# schematic_design.net
KiCad netlist of a schematic drawn in EAGLE
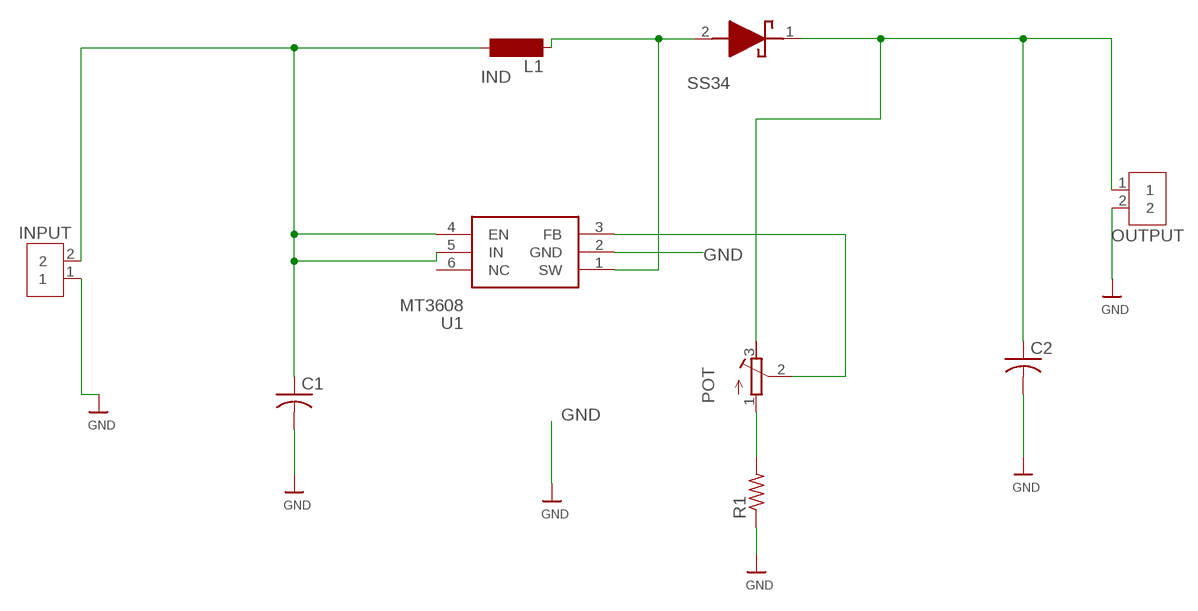
[diagram p0: schematic, sheet 1]

(export (version "E")
  (design (tool "Eeschema 10.0.6"))
  (components
    (comp (ref "C1")
      (value "C-USC0805")
      (footprint "eagle-import:C0805")
      (libsource (lib "eagle-import") (part "C-USC0805"))
    )
    (comp (ref "C2")
      (value "C-USC0805")
      (footprint "eagle-import:C0805")
      (libsource (lib "eagle-import") (part "C-USC0805"))
    )
    (comp (ref "D1")
      (value "SS34")
      (footprint "eagle-import:DIOM7959X262N")
      (fields (field (name "MOUSER_PART_NUMBER") "821-SS34"))
      (libsource (lib "eagle-import") (part "SS34"))
    )
    (comp (ref "INPUT")
      (value "2828XX-2282834-2")
      (footprint "eagle-import:TERMBLK_254-2N")
      (libsource (lib "eagle-import") (part "2828XX-2282834-2"))
    )
    (comp (ref "L1")
      (value "MS42")
      (footprint "eagle-import:MS42")
      (libsource (lib "eagle-import") (part "MS42"))
    )
    (comp (ref "OUTPUT")
      (value "2828XX-2282834-2")
      (footprint "eagle-import:TERMBLK_254-2N")
      (libsource (lib "eagle-import") (part "2828XX-2282834-2"))
    )
    (comp (ref "POT")
      (value "R-TRIMM3296W")
      (footprint "eagle-import:RTRIM3296W")
      (libsource (lib "eagle-import") (part "R-TRIMM3296W"))
    )
    (comp (ref "R1")
      (value "R-US_M0805")
      (footprint "eagle-import:M0805")
      (libsource (lib "eagle-import") (part "R-US_M0805"))
    )
    (comp (ref "U1")
      (value "MT3608")
      (footprint "eagle-import:SOT95P280X145-6N")
      (libsource (lib "eagle-import") (part "MT3608"))
    )
  )
  (nets
    (net (code "1") (name "/IND") (class "Default")
      (node (ref "D1") (pin "2") (pinfunction "A_2") (pintype "bidirectional"))
      (node (ref "L1") (pin "1") (pinfunction "1_1") (pintype "passive"))
      (node (ref "U1") (pin "1") (pinfunction "SW_1") (pintype "bidirectional"))
    )
    (net (code "2") (name "GND") (class "Default")
      (node (ref "C1") (pin "2") (pinfunction "2_2") (pintype "passive"))
      (node (ref "C2") (pin "2") (pinfunction "2_2") (pintype "passive"))
      (node (ref "INPUT") (pin "1") (pinfunction "1_1") (pintype "bidirectional"))
      (node (ref "OUTPUT") (pin "2") (pinfunction "2_2") (pintype "bidirectional"))
      (node (ref "R1") (pin "1") (pinfunction "1_1") (pintype "passive"))
      (node (ref "U1") (pin "2") (pinfunction "GND_2") (pintype "bidirectional"))
    )
    (net (code "3") (name "Net-(D1-K)") (class "Default")
      (node (ref "C2") (pin "1") (pinfunction "1_1") (pintype "passive"))
      (node (ref "D1") (pin "1") (pinfunction "K_1") (pintype "bidirectional"))
      (node (ref "OUTPUT") (pin "1") (pinfunction "1_1") (pintype "bidirectional"))
      (node (ref "POT") (pin "3") (pinfunction "E_3") (pintype "passive"))
    )
    (net (code "4") (name "Net-(POT-A)") (class "Default")
      (node (ref "POT") (pin "1") (pinfunction "A_1") (pintype "passive"))
      (node (ref "R1") (pin "2") (pinfunction "2_2") (pintype "passive"))
    )
    (net (code "5") (name "Net-(POT-S)") (class "Default")
      (node (ref "POT") (pin "2") (pinfunction "S_2") (pintype "passive"))
      (node (ref "U1") (pin "3") (pinfunction "FB_3") (pintype "bidirectional"))
    )
    (net (code "6") (name "Net-(U1-EN)") (class "Default")
      (node (ref "C1") (pin "1") (pinfunction "1_1") (pintype "passive"))
      (node (ref "INPUT") (pin "2") (pinfunction "2_2") (pintype "bidirectional"))
      (node (ref "L1") (pin "2") (pinfunction "2_2") (pintype "passive"))
      (node (ref "U1") (pin "4") (pinfunction "EN_4") (pintype "bidirectional"))
      (node (ref "U1") (pin "5") (pinfunction "IN_5") (pintype "bidirectional"))
    )
    (net (code "7") (name "unconnected-(U1-NC-Pad6)") (class "Default")
      (node (ref "U1") (pin "6") (pinfunction "NC_6") (pintype "no_connect"))
    )
  )
)
